# EasyEDAProject.net
KiCad netlist of a schematic drawn in EasyEDA
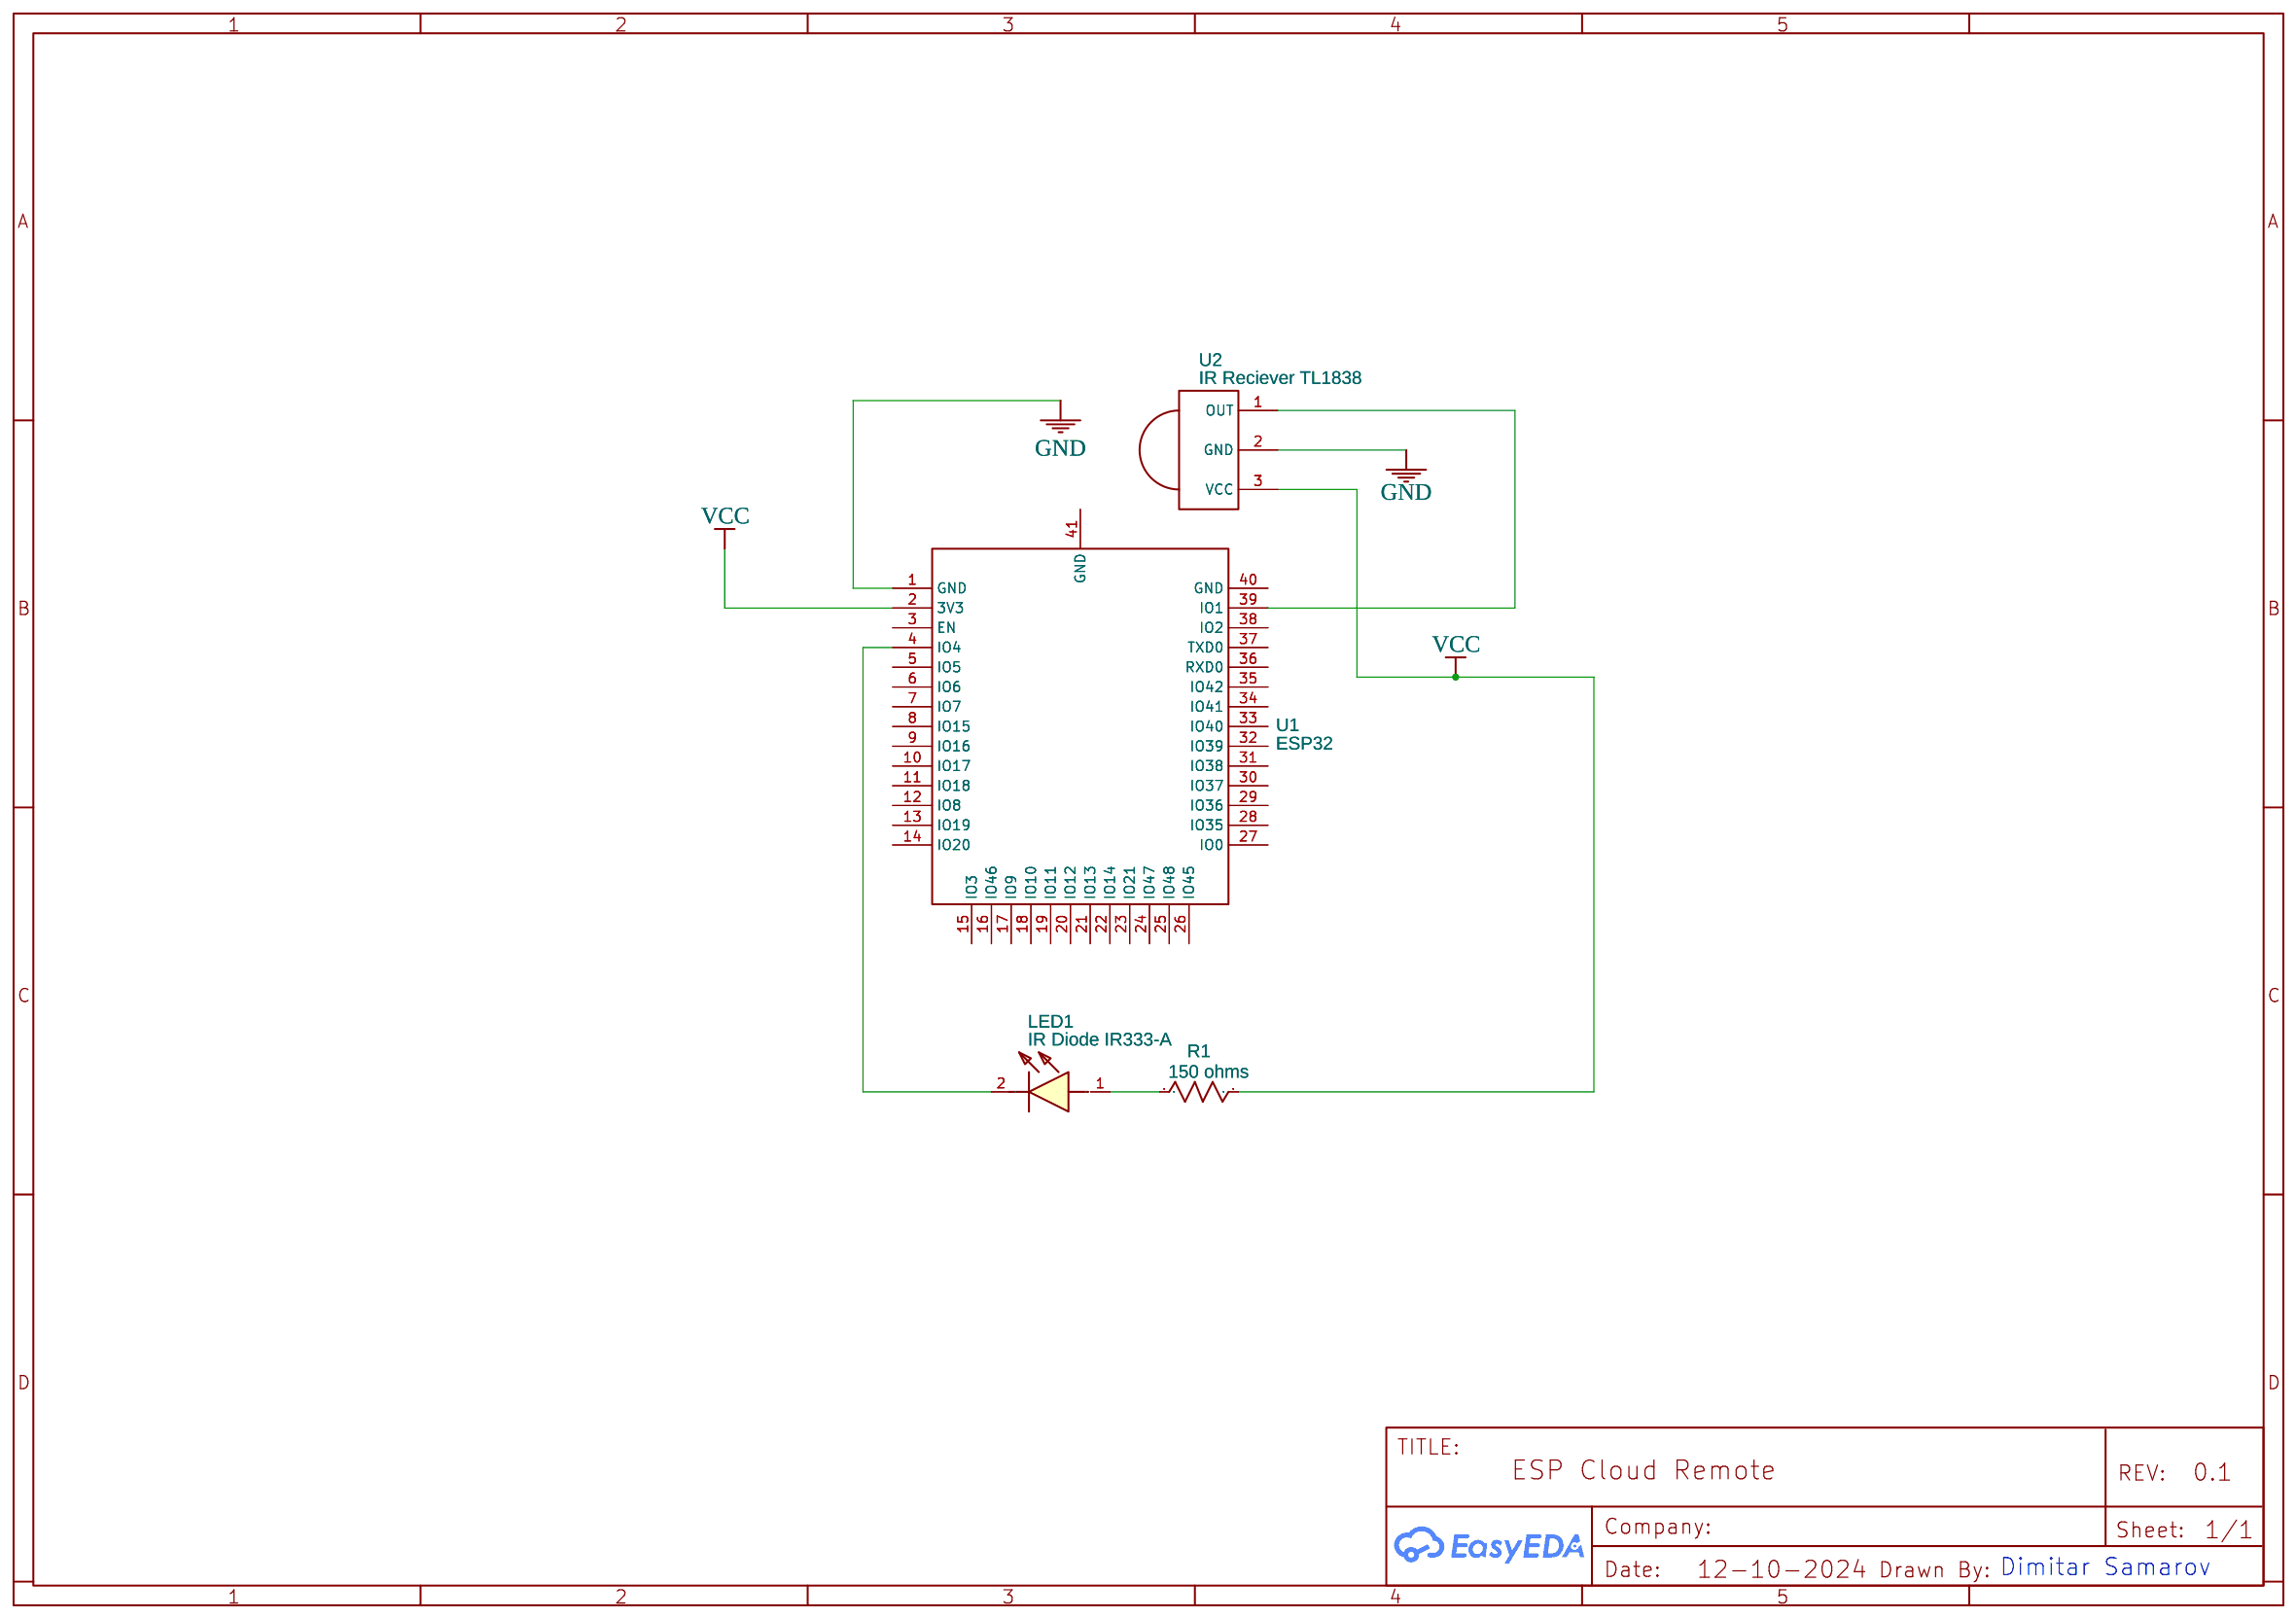
[diagram p0: schematic sheet]

(export (version "E")
  (design (tool "Eeschema 10.0.6"))
  (components
    (comp (ref "LED1") (value "IR Diode IR333-A") (libsource (lib "") (part "IR333-A")))
    (comp (ref "R1") (value "150 ohms") (libsource (lib "") (part "R_0603_US")))
    (comp (ref "U1")
      (value "ESP32")
      (fields
        (field (name "Manufacturer Part") "ESP32-S3-WROOM-1U-N4")
        (field (name "Manufacturer") "ESPRESSIF(乐鑫)")
      )
      (libsource (lib "") (part "ESP32-S3-WROOM-1U-N4"))
    )
    (comp (ref "U2") (value "IR Reciever TL1838") (libsource (lib "") (part "TL1838")))
  )
  (nets
    (net (code "1") (name "GND") (class "Default")
      (node (ref "U1") (pin "1") (pinfunction "GND_1") (pintype "passive"))
      (node (ref "U2") (pin "2") (pinfunction "GND_2") (pintype "unspecified"))
    )
    (net (code "2") (name "Net-(LED1-A)") (class "Default")
      (node (ref "LED1") (pin "1") (pinfunction "A_1") (pintype "bidirectional"))
      (node (ref "R1") (pin "1") (pinfunction "1_1") (pintype "unspecified"))
    )
    (net (code "3") (name "Net-(LED1-K)") (class "Default")
      (node (ref "LED1") (pin "2") (pinfunction "K_2") (pintype "bidirectional"))
      (node (ref "U1") (pin "4") (pinfunction "IO4_4") (pintype "unspecified"))
    )
    (net (code "4") (name "Net-(U1-IO1)") (class "Default")
      (node (ref "U1") (pin "39") (pinfunction "IO1_39") (pintype "unspecified"))
      (node (ref "U2") (pin "1") (pinfunction "OUT_1") (pintype "unspecified"))
    )
    (net (code "5") (name "VCC") (class "Default")
      (node (ref "R1") (pin "2") (pinfunction "2_2") (pintype "unspecified"))
      (node (ref "U1") (pin "2") (pinfunction "3V3_2") (pintype "passive"))
      (node (ref "U2") (pin "3") (pinfunction "VCC_3") (pintype "unspecified"))
    )
    (net (code "6") (name "unconnected-(U1-EN-Pad3)") (class "Default")
      (node (ref "U1") (pin "3") (pinfunction "EN_3") (pintype "unspecified"))
    )
    (net (code "7") (name "unconnected-(U1-GND-Pad40)") (class "Default")
      (node (ref "U1") (pin "40") (pinfunction "GND_40") (pintype "passive"))
    )
    (net (code "8") (name "unconnected-(U1-GND-Pad41)") (class "Default")
      (node (ref "U1") (pin "41") (pinfunction "GND_41") (pintype "passive"))
    )
    (net (code "9") (name "unconnected-(U1-IO0-Pad27)") (class "Default")
      (node (ref "U1") (pin "27") (pinfunction "IO0_27") (pintype "unspecified"))
    )
    (net (code "10") (name "unconnected-(U1-IO2-Pad38)") (class "Default")
      (node (ref "U1") (pin "38") (pinfunction "IO2_38") (pintype "unspecified"))
    )
    (net (code "11") (name "unconnected-(U1-IO3-Pad15)") (class "Default")
      (node (ref "U1") (pin "15") (pinfunction "IO3_15") (pintype "unspecified"))
    )
    (net (code "12") (name "unconnected-(U1-IO5-Pad5)") (class "Default")
      (node (ref "U1") (pin "5") (pinfunction "IO5_5") (pintype "unspecified"))
    )
    (net (code "13") (name "unconnected-(U1-IO6-Pad6)") (class "Default")
      (node (ref "U1") (pin "6") (pinfunction "IO6_6") (pintype "unspecified"))
    )
    (net (code "14") (name "unconnected-(U1-IO7-Pad7)") (class "Default")
      (node (ref "U1") (pin "7") (pinfunction "IO7_7") (pintype "unspecified"))
    )
    (net (code "15") (name "unconnected-(U1-IO8-Pad12)") (class "Default")
      (node (ref "U1") (pin "12") (pinfunction "IO8_12") (pintype "unspecified"))
    )
    (net (code "16") (name "unconnected-(U1-IO9-Pad17)") (class "Default")
      (node (ref "U1") (pin "17") (pinfunction "IO9_17") (pintype "unspecified"))
    )
    (net (code "17") (name "unconnected-(U1-IO10-Pad18)") (class "Default")
      (node (ref "U1") (pin "18") (pinfunction "IO10_18") (pintype "unspecified"))
    )
    (net (code "18") (name "unconnected-(U1-IO11-Pad19)") (class "Default")
      (node (ref "U1") (pin "19") (pinfunction "IO11_19") (pintype "unspecified"))
    )
    (net (code "19") (name "unconnected-(U1-IO12-Pad20)") (class "Default")
      (node (ref "U1") (pin "20") (pinfunction "IO12_20") (pintype "unspecified"))
    )
    (net (code "20") (name "unconnected-(U1-IO13-Pad21)") (class "Default")
      (node (ref "U1") (pin "21") (pinfunction "IO13_21") (pintype "unspecified"))
    )
    (net (code "21") (name "unconnected-(U1-IO14-Pad22)") (class "Default")
      (node (ref "U1") (pin "22") (pinfunction "IO14_22") (pintype "unspecified"))
    )
    (net (code "22") (name "unconnected-(U1-IO15-Pad8)") (class "Default")
      (node (ref "U1") (pin "8") (pinfunction "IO15_8") (pintype "unspecified"))
    )
    (net (code "23") (name "unconnected-(U1-IO16-Pad9)") (class "Default")
      (node (ref "U1") (pin "9") (pinfunction "IO16_9") (pintype "unspecified"))
    )
    (net (code "24") (name "unconnected-(U1-IO17-Pad10)") (class "Default")
      (node (ref "U1") (pin "10") (pinfunction "IO17_10") (pintype "unspecified"))
    )
    (net (code "25") (name "unconnected-(U1-IO18-Pad11)") (class "Default")
      (node (ref "U1") (pin "11") (pinfunction "IO18_11") (pintype "unspecified"))
    )
    (net (code "26") (name "unconnected-(U1-IO19-Pad13)") (class "Default")
      (node (ref "U1") (pin "13") (pinfunction "IO19_13") (pintype "unspecified"))
    )
    (net (code "27") (name "unconnected-(U1-IO20-Pad14)") (class "Default")
      (node (ref "U1") (pin "14") (pinfunction "IO20_14") (pintype "unspecified"))
    )
    (net (code "28") (name "unconnected-(U1-IO21-Pad23)") (class "Default")
      (node (ref "U1") (pin "23") (pinfunction "IO21_23") (pintype "unspecified"))
    )
    (net (code "29") (name "unconnected-(U1-IO35-Pad28)") (class "Default")
      (node (ref "U1") (pin "28") (pinfunction "IO35_28") (pintype "unspecified"))
    )
    (net (code "30") (name "unconnected-(U1-IO36-Pad29)") (class "Default")
      (node (ref "U1") (pin "29") (pinfunction "IO36_29") (pintype "unspecified"))
    )
    (net (code "31") (name "unconnected-(U1-IO37-Pad30)") (class "Default")
      (node (ref "U1") (pin "30") (pinfunction "IO37_30") (pintype "unspecified"))
    )
    (net (code "32") (name "unconnected-(U1-IO38-Pad31)") (class "Default")
      (node (ref "U1") (pin "31") (pinfunction "IO38_31") (pintype "unspecified"))
    )
    (net (code "33") (name "unconnected-(U1-IO39-Pad32)") (class "Default")
      (node (ref "U1") (pin "32") (pinfunction "IO39_32") (pintype "unspecified"))
    )
    (net (code "34") (name "unconnected-(U1-IO40-Pad33)") (class "Default")
      (node (ref "U1") (pin "33") (pinfunction "IO40_33") (pintype "unspecified"))
    )
    (net (code "35") (name "unconnected-(U1-IO41-Pad34)") (class "Default")
      (node (ref "U1") (pin "34") (pinfunction "IO41_34") (pintype "unspecified"))
    )
    (net (code "36") (name "unconnected-(U1-IO42-Pad35)") (class "Default")
      (node (ref "U1") (pin "35") (pinfunction "IO42_35") (pintype "unspecified"))
    )
    (net (code "37") (name "unconnected-(U1-IO45-Pad26)") (class "Default")
      (node (ref "U1") (pin "26") (pinfunction "IO45_26") (pintype "unspecified"))
    )
    (net (code "38") (name "unconnected-(U1-IO46-Pad16)") (class "Default")
      (node (ref "U1") (pin "16") (pinfunction "IO46_16") (pintype "unspecified"))
    )
    (net (code "39") (name "unconnected-(U1-IO47-Pad24)") (class "Default")
      (node (ref "U1") (pin "24") (pinfunction "IO47_24") (pintype "unspecified"))
    )
    (net (code "40") (name "unconnected-(U1-IO48-Pad25)") (class "Default")
      (node (ref "U1") (pin "25") (pinfunction "IO48_25") (pintype "unspecified"))
    )
    (net (code "41") (name "unconnected-(U1-RXD0-Pad36)") (class "Default")
      (node (ref "U1") (pin "36") (pinfunction "RXD0_36") (pintype "unspecified"))
    )
    (net (code "42") (name "unconnected-(U1-TXD0-Pad37)") (class "Default")
      (node (ref "U1") (pin "37") (pinfunction "TXD0_37") (pintype "unspecified"))
    )
  )
)
